# ADC.net
KiCad netlist of a schematic drawn in Altium Designer
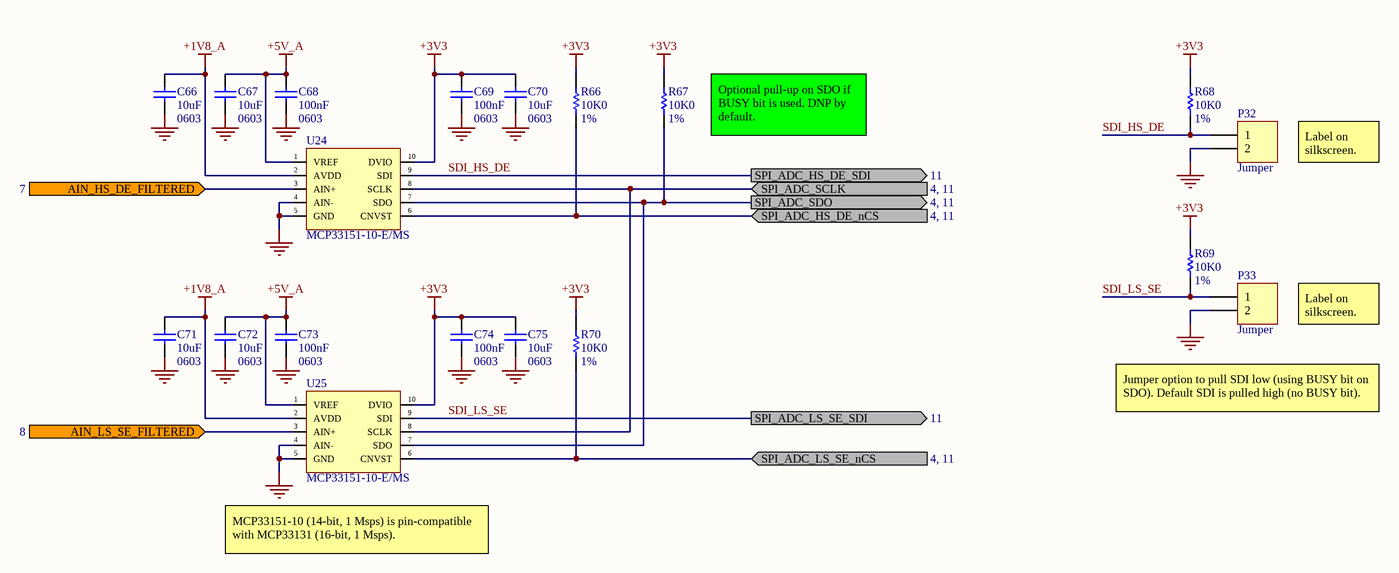
[diagram p0: ADC.SchDoc]

(export (version "E")
  (design (tool "Eeschema 10.0.6"))
  (components
    (comp (ref "C66")
      (value "10uF")
      (footprint "0603 CAP SAMSUNG CL10C")
      (description "Capacitor")
      (fields (field (name "ALTIUM_VALUE") "0603") (field (name "PUBLISHER") "Altium Limited"))
      (libsource (lib "Miscellaneous Devices") (part "Cap"))
    )
    (comp (ref "C67")
      (value "10uF")
      (footprint "0603 CAP SAMSUNG CL10C")
      (description "Capacitor")
      (fields (field (name "ALTIUM_VALUE") "0603") (field (name "PUBLISHER") "Altium Limited"))
      (libsource (lib "Miscellaneous Devices") (part "Cap"))
    )
    (comp (ref "C68")
      (value "100nF")
      (footprint "0603 CAP SAMSUNG CL10C")
      (description "Capacitor")
      (fields (field (name "ALTIUM_VALUE") "0603") (field (name "PUBLISHER") "Altium Limited"))
      (libsource (lib "Miscellaneous Devices") (part "Cap"))
    )
    (comp (ref "C69")
      (value "100nF")
      (footprint "0603 CAP SAMSUNG CL10C")
      (description "Capacitor")
      (fields (field (name "ALTIUM_VALUE") "0603") (field (name "PUBLISHER") "Altium Limited"))
      (libsource (lib "Miscellaneous Devices") (part "Cap"))
    )
    (comp (ref "C70")
      (value "10uF")
      (footprint "0603 CAP SAMSUNG CL10C")
      (description "Capacitor")
      (fields (field (name "ALTIUM_VALUE") "0603") (field (name "PUBLISHER") "Altium Limited"))
      (libsource (lib "Miscellaneous Devices") (part "Cap"))
    )
    (comp (ref "C71")
      (value "10uF")
      (footprint "0603 CAP SAMSUNG CL10C")
      (description "Capacitor")
      (fields (field (name "ALTIUM_VALUE") "0603") (field (name "PUBLISHER") "Altium Limited"))
      (libsource (lib "Miscellaneous Devices") (part "Cap"))
    )
    (comp (ref "C72")
      (value "10uF")
      (footprint "0603 CAP SAMSUNG CL10C")
      (description "Capacitor")
      (fields (field (name "ALTIUM_VALUE") "0603") (field (name "PUBLISHER") "Altium Limited"))
      (libsource (lib "Miscellaneous Devices") (part "Cap"))
    )
    (comp (ref "C73")
      (value "100nF")
      (footprint "0603 CAP SAMSUNG CL10C")
      (description "Capacitor")
      (fields (field (name "ALTIUM_VALUE") "0603") (field (name "PUBLISHER") "Altium Limited"))
      (libsource (lib "Miscellaneous Devices") (part "Cap"))
    )
    (comp (ref "C74")
      (value "100nF")
      (footprint "0603 CAP SAMSUNG CL10C")
      (description "Capacitor")
      (fields (field (name "ALTIUM_VALUE") "0603") (field (name "PUBLISHER") "Altium Limited"))
      (libsource (lib "Miscellaneous Devices") (part "Cap"))
    )
    (comp (ref "C75")
      (value "10uF")
      (footprint "0603 CAP SAMSUNG CL10C")
      (description "Capacitor")
      (fields (field (name "ALTIUM_VALUE") "0603") (field (name "PUBLISHER") "Altium Limited"))
      (libsource (lib "Miscellaneous Devices") (part "Cap"))
    )
    (comp (ref "P32")
      (value "Jumper")
      (footprint "HDR1X2")
      (description "Header, 2-Pin")
      (fields (field (name "PUBLISHER") "Altium Limited"))
      (libsource (lib "Miscellaneous Connectors") (part "Header 2"))
    )
    (comp (ref "P33")
      (value "Jumper")
      (footprint "HDR1X2")
      (description "Header, 2-Pin")
      (fields (field (name "PUBLISHER") "Altium Limited"))
      (libsource (lib "Miscellaneous Connectors") (part "Header 2"))
    )
    (comp (ref "R66")
      (value "10K0")
      (footprint "0603 RES")
      (description "Resistor")
      (fields (field (name "ALTIUM_VALUE") "1%") (field (name "PUBLISHER") "Altium Limited"))
      (libsource (lib "Miscellaneous Devices") (part "Res1"))
    )
    (comp (ref "R67")
      (value "10K0")
      (footprint "0603 RES")
      (description "Resistor")
      (fields (field (name "ALTIUM_VALUE") "1%") (field (name "PUBLISHER") "Altium Limited"))
      (libsource (lib "Miscellaneous Devices") (part "Res1"))
    )
    (comp (ref "R68")
      (value "10K0")
      (footprint "0603 RES")
      (description "Resistor")
      (fields (field (name "ALTIUM_VALUE") "1%") (field (name "PUBLISHER") "Altium Limited"))
      (libsource (lib "Miscellaneous Devices") (part "Res1"))
    )
    (comp (ref "R69")
      (value "10K0")
      (footprint "0603 RES")
      (description "Resistor")
      (fields (field (name "ALTIUM_VALUE") "1%") (field (name "PUBLISHER") "Altium Limited"))
      (libsource (lib "Miscellaneous Devices") (part "Res1"))
    )
    (comp (ref "R70")
      (value "10K0")
      (footprint "0603 RES")
      (description "Resistor")
      (fields (field (name "ALTIUM_VALUE") "1%") (field (name "PUBLISHER") "Altium Limited"))
      (libsource (lib "Miscellaneous Devices") (part "Res1"))
    )
    (comp (ref "U24")
      (value "MCP33151-10-E/MS")
      (footprint "MSOP-10")
      (description "ADC 14-bit SAR 1Msps 10-MSOP")
      (fields (field (name "MANUFACTURER") "Microchip"))
      (libsource (lib "MRT SCH Library") (part "ADC MCP33151"))
    )
    (comp (ref "U25")
      (value "MCP33151-10-E/MS")
      (footprint "MSOP-10")
      (description "ADC 14-bit SAR 1Msps 10-MSOP")
      (fields (field (name "MANUFACTURER") "Microchip"))
      (libsource (lib "MRT SCH Library") (part "ADC MCP33151"))
    )
  )
  (nets
    (net (code "1") (name "+1V8_A") (class "Default")
      (node (ref "C66") (pin "2") (pinfunction "2_2") (pintype "passive"))
      (node (ref "C71") (pin "2") (pinfunction "2_2") (pintype "passive"))
      (node (ref "U24") (pin "2") (pinfunction "AVDD_2") (pintype "passive"))
      (node (ref "U25") (pin "2") (pinfunction "AVDD_2") (pintype "passive"))
    )
    (net (code "2") (name "+3V3") (class "Default")
      (node (ref "C69") (pin "2") (pinfunction "2_2") (pintype "passive"))
      (node (ref "C70") (pin "2") (pinfunction "2_2") (pintype "passive"))
      (node (ref "C74") (pin "2") (pinfunction "2_2") (pintype "passive"))
      (node (ref "C75") (pin "2") (pinfunction "2_2") (pintype "passive"))
      (node (ref "R66") (pin "2") (pinfunction "2_2") (pintype "passive"))
      (node (ref "R67") (pin "2") (pinfunction "2_2") (pintype "passive"))
      (node (ref "R68") (pin "2") (pinfunction "2_2") (pintype "passive"))
      (node (ref "R69") (pin "2") (pinfunction "2_2") (pintype "passive"))
      (node (ref "R70") (pin "2") (pinfunction "2_2") (pintype "passive"))
      (node (ref "U24") (pin "10") (pinfunction "DVIO_10") (pintype "passive"))
      (node (ref "U25") (pin "10") (pinfunction "DVIO_10") (pintype "passive"))
    )
    (net (code "3") (name "+5V_A") (class "Default")
      (node (ref "C67") (pin "2") (pinfunction "2_2") (pintype "passive"))
      (node (ref "C68") (pin "2") (pinfunction "2_2") (pintype "passive"))
      (node (ref "C72") (pin "2") (pinfunction "2_2") (pintype "passive"))
      (node (ref "C73") (pin "2") (pinfunction "2_2") (pintype "passive"))
      (node (ref "U24") (pin "1") (pinfunction "VREF_1") (pintype "passive"))
      (node (ref "U25") (pin "1") (pinfunction "VREF_1") (pintype "passive"))
    )
    (net (code "4") (name "/AIN_HS_DE_FILTERED") (class "Default")
      (node (ref "U24") (pin "3") (pinfunction "AIN+_3") (pintype "passive"))
    )
    (net (code "5") (name "/AIN_LS_SE_FILTERED") (class "Default")
      (node (ref "U25") (pin "3") (pinfunction "AIN+_3") (pintype "passive"))
    )
    (net (code "6") (name "/SDI_HS_DE") (class "Default")
      (node (ref "P32") (pin "1") (pinfunction "1_1") (pintype "passive"))
      (node (ref "R68") (pin "1") (pinfunction "1_1") (pintype "passive"))
      (node (ref "U24") (pin "9") (pinfunction "SDI_9") (pintype "passive"))
    )
    (net (code "7") (name "/SDI_LS_SE") (class "Default")
      (node (ref "P33") (pin "1") (pinfunction "1_1") (pintype "passive"))
      (node (ref "R69") (pin "1") (pinfunction "1_1") (pintype "passive"))
      (node (ref "U25") (pin "9") (pinfunction "SDI_9") (pintype "passive"))
    )
    (net (code "8") (name "/SPI_ADC_HS_DE_nCS") (class "Default")
      (node (ref "R66") (pin "1") (pinfunction "1_1") (pintype "passive"))
      (node (ref "U24") (pin "6") (pinfunction "CNVST_6") (pintype "passive"))
    )
    (net (code "9") (name "/SPI_ADC_LS_SE_nCS") (class "Default")
      (node (ref "R70") (pin "1") (pinfunction "1_1") (pintype "passive"))
      (node (ref "U25") (pin "6") (pinfunction "CNVST_6") (pintype "passive"))
    )
    (net (code "10") (name "/SPI_ADC_SCLK") (class "Default")
      (node (ref "U24") (pin "8") (pinfunction "SCLK_8") (pintype "passive"))
      (node (ref "U25") (pin "8") (pinfunction "SCLK_8") (pintype "passive"))
    )
    (net (code "11") (name "/SPI_ADC_SDO") (class "Default")
      (node (ref "R67") (pin "1") (pinfunction "1_1") (pintype "passive"))
      (node (ref "U24") (pin "7") (pinfunction "SDO_7") (pintype "passive"))
      (node (ref "U25") (pin "7") (pinfunction "SDO_7") (pintype "passive"))
    )
    (net (code "12") (name "GND") (class "Default")
      (node (ref "C66") (pin "1") (pinfunction "1_1") (pintype "passive"))
      (node (ref "C67") (pin "1") (pinfunction "1_1") (pintype "passive"))
      (node (ref "C68") (pin "1") (pinfunction "1_1") (pintype "passive"))
      (node (ref "C69") (pin "1") (pinfunction "1_1") (pintype "passive"))
      (node (ref "C70") (pin "1") (pinfunction "1_1") (pintype "passive"))
      (node (ref "C71") (pin "1") (pinfunction "1_1") (pintype "passive"))
      (node (ref "C72") (pin "1") (pinfunction "1_1") (pintype "passive"))
      (node (ref "C73") (pin "1") (pinfunction "1_1") (pintype "passive"))
      (node (ref "C74") (pin "1") (pinfunction "1_1") (pintype "passive"))
      (node (ref "C75") (pin "1") (pinfunction "1_1") (pintype "passive"))
      (node (ref "P32") (pin "2") (pinfunction "2_2") (pintype "passive"))
      (node (ref "P33") (pin "2") (pinfunction "2_2") (pintype "passive"))
      (node (ref "U24") (pin "4") (pinfunction "AIN-_4") (pintype "passive"))
      (node (ref "U24") (pin "5") (pinfunction "GND_5") (pintype "passive"))
      (node (ref "U25") (pin "4") (pinfunction "AIN-_4") (pintype "passive"))
      (node (ref "U25") (pin "5") (pinfunction "GND_5") (pintype "passive"))
    )
  )
)
